# atmega.net
KiCad netlist of a schematic drawn in Altium Designer
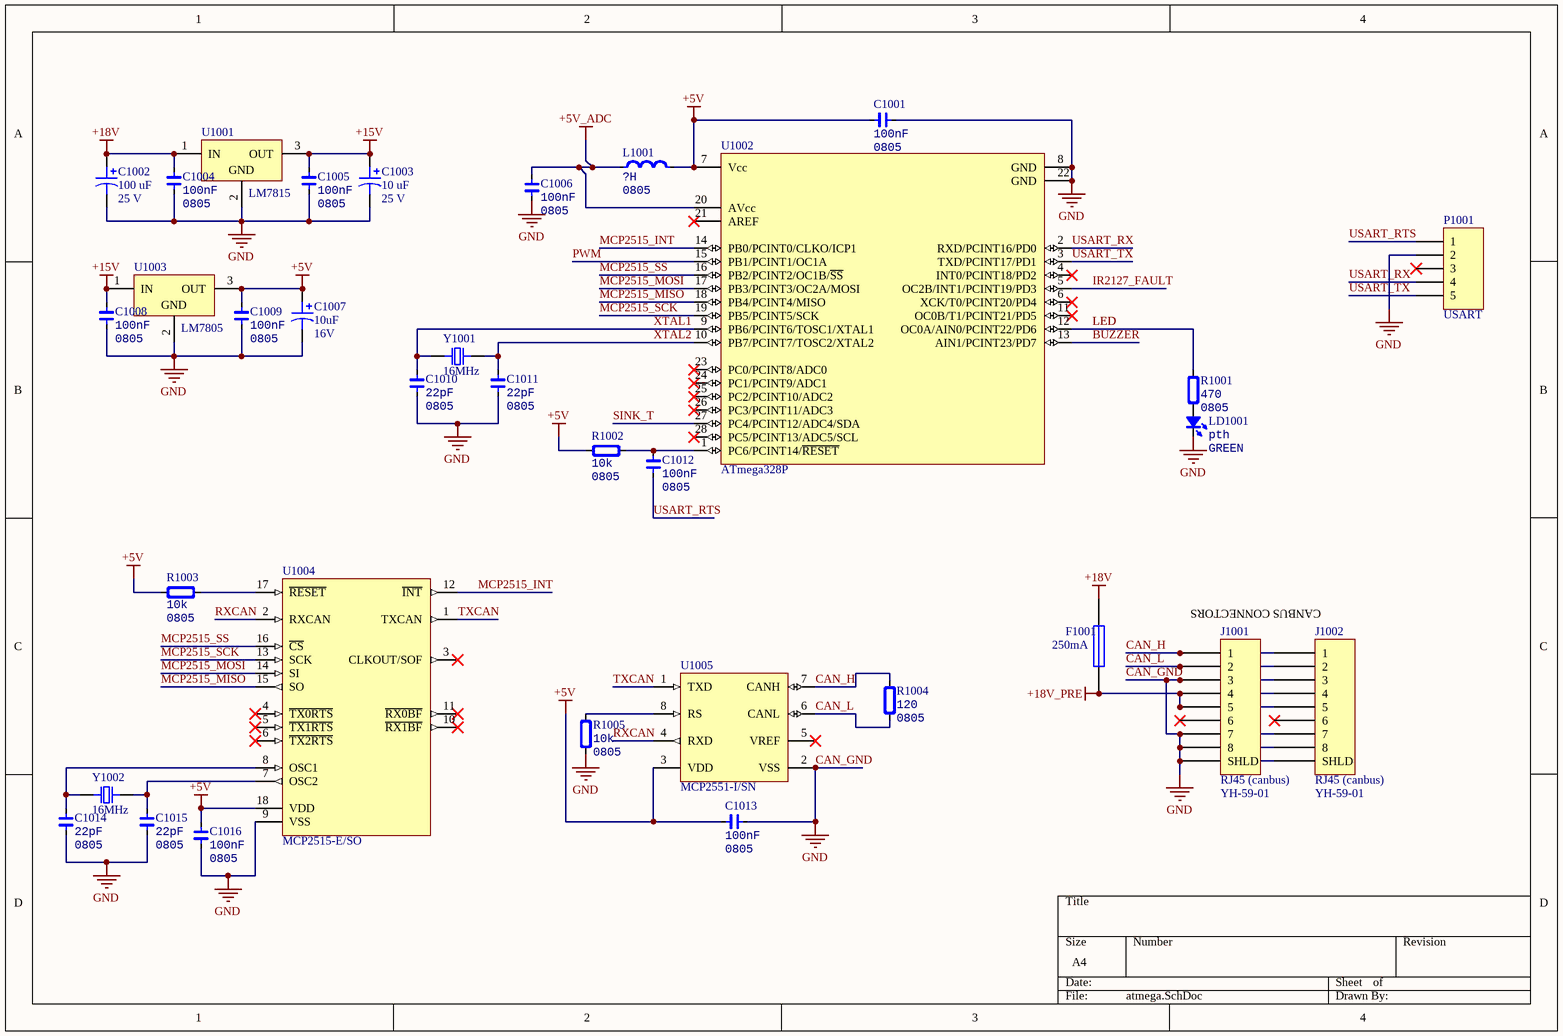
[diagram p0: atmega.SchDoc]

(export (version "E")
  (design (tool "Eeschema 10.0.6"))
  (components
    (comp (ref "C1001")
      (value "100nF")
      (footprint "0805C")
      (description "Capacitor")
      (fields (field (name "TYPE") "0805"))
      (libsource (lib "") (part "Cap_0805_2"))
    )
    (comp (ref "C1002")
      (value "100 uF")
      (footprint "CP3.5mm-8.0mm")
      (description "Solid Aluminum Capacitor with Organic Semiconductor Electrolyte: 100uF, 10V, Bulk Pack")
      (fields (field (name "VOLTAGE") "25 V") (field (name "Comment") "CapacitorPol"))
      (libsource (lib "R2R - Nova") (part "CapacitorPol"))
    )
    (comp (ref "C1003")
      (value "10 uF")
      (footprint "CP3.5mm-8.0mm")
      (description "Solid Aluminum Capacitor with Organic Semiconductor Electrolyte: 100uF, 10V, Bulk Pack")
      (fields (field (name "VOLTAGE") "25 V") (field (name "Comment") "CapacitorPol"))
      (libsource (lib "R2R - Nova") (part "CapacitorPol"))
    )
    (comp (ref "C1004")
      (value "100nF")
      (footprint "0805C")
      (description "Capacitor")
      (fields (field (name "TYPE") "0805"))
      (libsource (lib "SCH_Passive") (part "Cap_0805"))
    )
    (comp (ref "C1005")
      (value "100nF")
      (footprint "0805C")
      (description "Capacitor")
      (fields (field (name "TYPE") "0805"))
      (libsource (lib "SCH_Passive") (part "Cap_0805"))
    )
    (comp (ref "C1006")
      (value "100nF")
      (footprint "0805C")
      (description "Capacitor")
      (fields (field (name "TYPE") "0805"))
      (libsource (lib "SCH_Passive") (part "Cap_0805"))
    )
    (comp (ref "C1007")
      (value "10uF")
      (footprint "CP3.5mm-8.0mm")
      (description "Solid Aluminum Capacitor with Organic Semiconductor Electrolyte: 100uF, 10V, Bulk Pack")
      (fields (field (name "VOLTAGE") "16V") (field (name "Comment") "CapacitorPol"))
      (libsource (lib "R2R - Nova") (part "CapacitorPol"))
    )
    (comp (ref "C1008")
      (value "100nF")
      (footprint "0805C")
      (description "Capacitor")
      (fields (field (name "TYPE") "0805"))
      (libsource (lib "SCH_Passive") (part "Cap_0805"))
    )
    (comp (ref "C1009")
      (value "100nF")
      (footprint "0805C")
      (description "Capacitor")
      (fields (field (name "TYPE") "0805"))
      (libsource (lib "SCH_Passive") (part "Cap_0805"))
    )
    (comp (ref "C1010")
      (value "22pF")
      (footprint "0805C")
      (description "Capacitor")
      (fields (field (name "TYPE") "0805"))
      (libsource (lib "SCH_Passive") (part "Cap_0805"))
    )
    (comp (ref "C1011")
      (value "22pF")
      (footprint "0805C")
      (description "Capacitor")
      (fields (field (name "TYPE") "0805"))
      (libsource (lib "SCH_Passive") (part "Cap_0805"))
    )
    (comp (ref "C1012")
      (value "100nF")
      (footprint "0805C")
      (description "Capacitor")
      (fields (field (name "TYPE") "0805"))
      (libsource (lib "") (part "Cap_0805_1"))
    )
    (comp (ref "C1013")
      (value "100nF")
      (footprint "0805C")
      (description "Capacitor")
      (fields (field (name "TYPE") "0805"))
      (libsource (lib "") (part "Cap_0805_2"))
    )
    (comp (ref "C1014")
      (value "22pF")
      (footprint "0805C")
      (description "Capacitor")
      (fields (field (name "TYPE") "0805"))
      (libsource (lib "SCH_Passive") (part "Cap_0805"))
    )
    (comp (ref "C1015")
      (value "22pF")
      (footprint "0805C")
      (description "Capacitor")
      (fields (field (name "TYPE") "0805"))
      (libsource (lib "SCH_Passive") (part "Cap_0805"))
    )
    (comp (ref "C1016")
      (value "100nF")
      (footprint "0805C")
      (description "Capacitor")
      (fields (field (name "TYPE") "0805"))
      (libsource (lib "") (part "Cap_0805_1"))
    )
    (comp (ref "F1001")
      (value "250mA")
      (footprint "Porta Fusivel")
      (description "Fuse")
      (libsource (lib "Miscellaneous Devices") (part "Fuse 1"))
    )
    (comp (ref "J1001")
      (value "RJ45 (canbus)")
      (footprint "ASSMANN A-2004-2-4-LP/FS")
      (description "YH-59-01")
      (fields (field (name "ALTIUM_VALUE") "YH-59-01"))
      (libsource (lib "Connectors") (part "Modular Jack with Shield"))
    )
    (comp (ref "J1002")
      (value "RJ45 (canbus)")
      (footprint "ASSMANN A-2004-2-4-LP/FS")
      (description "YH-59-01")
      (fields (field (name "ALTIUM_VALUE") "YH-59-01"))
      (libsource (lib "Connectors") (part "Modular Jack with Shield"))
    )
    (comp (ref "L1001")
      (value "?H")
      (footprint "0805L")
      (description "Inductor")
      (fields (field (name "TYPE") "0805"))
      (libsource (lib "SCH_Passive") (part "Ind_0805"))
    )
    (comp (ref "LD1001")
      (value "GREEN")
      (footprint "LED3MM")
      (description "LED")
      (fields (field (name "TYPE") "pth"))
      (libsource (lib "SCH_Active") (part "LED_0805"))
    )
    (comp (ref "P1001")
      (value "USART")
      (footprint "Zenite_Footprints:HDR1X5")
      (description "Header, 5-Pin")
      (libsource (lib "R2R - Nova") (part "Header 5"))
    )
    (comp (ref "R1001")
      (value "470")
      (footprint "0805R")
      (description "Resistor")
      (fields (field (name "TYPE") "0805"))
      (libsource (lib "SCH_Passive") (part "Res_0805"))
    )
    (comp (ref "R1002")
      (value "10k")
      (footprint "0805R")
      (description "Resistor")
      (fields (field (name "TYPE") "0805"))
      (libsource (lib "SCH_Passive") (part "Res_0805"))
    )
    (comp (ref "R1003")
      (value "10k")
      (footprint "0805R")
      (description "Resistor")
      (fields (field (name "TYPE") "0805"))
      (libsource (lib "SCH_Passive") (part "Res_0805"))
    )
    (comp (ref "R1004")
      (value "120")
      (footprint "0805R")
      (description "Resistor")
      (fields (field (name "TYPE") "0805"))
      (libsource (lib "SCH_Passive") (part "Res_0805"))
    )
    (comp (ref "R1005")
      (value "10k")
      (footprint "0805R")
      (description "Resistor")
      (fields (field (name "TYPE") "0805"))
      (libsource (lib "SCH_Passive") (part "Res_0805"))
    )
    (comp (ref "U1001")
      (value "LM7815")
      (footprint "TO220_deitado")
      (description "Positive-Voltage Regulator")
      (libsource (lib "TI Power Mgt Voltage Regulator") (part "µA7805CKC"))
    )
    (comp (ref "U1002")
      (value "ATmega328P")
      (footprint "DIP28-300(100)")
      (libsource (lib "R2R - Nova") (part "ATmega328P"))
    )
    (comp (ref "U1003")
      (value "LM7805")
      (footprint "TO220_deitado")
      (description "Positive-Voltage Regulator")
      (libsource (lib "TI Power Mgt Voltage Regulator") (part "µA7805CKC"))
    )
    (comp (ref "U1004")
      (value "MCP2515-E/SO")
      (footprint "WSO18_L")
      (description "Stand-Alone CAN Controller With SPI Interface, 18-Pin SOIC, Extended Temperature")
      (libsource (lib "Altium Content Vault") (part "COM-CAN-MCP2515-18"))
    )
    (comp (ref "U1005")
      (value "MCP2551-I/SN")
      (footprint "SOIC08-150(50)")
      (libsource (lib "Altium Content Vault") (part "MCHP-MCP2551-SN8"))
    )
    (comp (ref "Y1001")
      (value "16MHz")
      (footprint "HC49-US-THT")
      (description "Crystal")
      (libsource (lib "R2R - Nova") (part "Crystal"))
    )
    (comp (ref "Y1002")
      (value "16MHz")
      (footprint "HC49-US-THT")
      (description "Crystal")
      (libsource (lib "R2R - Nova") (part "Crystal"))
    )
  )
  (nets
    (net (code "1") (name "+5V") (class "Default")
      (node (ref "C1001") (pin "1") (pinfunction "1_1") (pintype "passive"))
      (node (ref "C1007") (pin "1") (pinfunction "1_1") (pintype "passive"))
      (node (ref "C1009") (pin "2") (pinfunction "2_2") (pintype "passive"))
      (node (ref "C1013") (pin "1") (pinfunction "1_1") (pintype "passive"))
      (node (ref "C1016") (pin "1") (pinfunction "1_1") (pintype "passive"))
      (node (ref "L1001") (pin "2") (pinfunction "2_2") (pintype "passive"))
      (node (ref "R1002") (pin "1") (pinfunction "1_1") (pintype "passive"))
      (node (ref "R1003") (pin "1") (pinfunction "1_1") (pintype "passive"))
      (node (ref "U1002") (pin "7") (pinfunction "Vcc_7") (pintype "passive"))
      (node (ref "U1003") (pin "3") (pinfunction "OUT_3") (pintype "power_in"))
      (node (ref "U1004") (pin "18") (pinfunction "VDD_18") (pintype "power_in"))
      (node (ref "U1005") (pin "3") (pinfunction "VDD_3") (pintype "power_in"))
    )
    (net (code "2") (name "+5V_ADC") (class "Default")
      (node (ref "C1006") (pin "2") (pinfunction "2_2") (pintype "passive"))
      (node (ref "L1001") (pin "1") (pinfunction "1_1") (pintype "passive"))
      (node (ref "U1002") (pin "20") (pinfunction "AVcc_20") (pintype "passive"))
    )
    (net (code "3") (name "+15V") (class "Default")
      (node (ref "C1003") (pin "1") (pinfunction "1_1") (pintype "passive"))
      (node (ref "C1005") (pin "2") (pinfunction "2_2") (pintype "passive"))
      (node (ref "C1008") (pin "2") (pinfunction "2_2") (pintype "passive"))
      (node (ref "U1001") (pin "3") (pinfunction "OUT_3") (pintype "power_in"))
      (node (ref "U1003") (pin "1") (pinfunction "IN_1") (pintype "power_in"))
    )
    (net (code "4") (name "+18V") (class "Default")
      (node (ref "C1002") (pin "1") (pinfunction "1_1") (pintype "passive"))
      (node (ref "C1004") (pin "2") (pinfunction "2_2") (pintype "passive"))
      (node (ref "F1001") (pin "1") (pinfunction "1_1") (pintype "passive"))
      (node (ref "U1001") (pin "1") (pinfunction "IN_1") (pintype "power_in"))
    )
    (net (code "5") (name "+18V_PRE") (class "Default")
      (node (ref "F1001") (pin "2") (pinfunction "2_2") (pintype "passive"))
      (node (ref "J1001") (pin "4") (pinfunction "4_4") (pintype "passive"))
      (node (ref "J1001") (pin "5") (pinfunction "5_5") (pintype "passive"))
      (node (ref "J1002") (pin "4") (pinfunction "4_4") (pintype "passive"))
      (node (ref "J1002") (pin "5") (pinfunction "5_5") (pintype "passive"))
    )
    (net (code "6") (name "/BUZZER") (class "Default")
      (node (ref "U1002") (pin "13") (pinfunction "AIN1/PCINT23/PD7_13") (pintype "bidirectional"))
    )
    (net (code "7") (name "/CAN_H") (class "Default")
      (node (ref "J1001") (pin "1") (pinfunction "1_1") (pintype "passive"))
      (node (ref "J1002") (pin "1") (pinfunction "1_1") (pintype "passive"))
      (node (ref "R1004") (pin "2") (pinfunction "2_2") (pintype "passive"))
      (node (ref "U1005") (pin "7") (pinfunction "CANH_7") (pintype "bidirectional"))
    )
    (net (code "8") (name "/CAN_L") (class "Default")
      (node (ref "J1001") (pin "2") (pinfunction "2_2") (pintype "passive"))
      (node (ref "J1002") (pin "2") (pinfunction "2_2") (pintype "passive"))
      (node (ref "R1004") (pin "1") (pinfunction "1_1") (pintype "passive"))
      (node (ref "U1005") (pin "6") (pinfunction "CANL_6") (pintype "bidirectional"))
    )
    (net (code "9") (name "/IR2127_FAULT") (class "Default")
      (node (ref "U1002") (pin "5") (pinfunction "OC2B/INT1/PCINT19/PD3_5") (pintype "bidirectional"))
    )
    (net (code "10") (name "/LED") (class "Default")
      (node (ref "R1001") (pin "2") (pinfunction "2_2") (pintype "passive"))
      (node (ref "U1002") (pin "12") (pinfunction "OC0A/AIN0/PCINT22/PD6_12") (pintype "bidirectional"))
    )
    (net (code "11") (name "/MCP2515_INT") (class "Default")
      (node (ref "U1002") (pin "14") (pinfunction "PB0/PCINT0/CLKO/ICP1_14") (pintype "bidirectional"))
      (node (ref "U1004") (pin "12") (pinfunction "~{INT}_12") (pintype "output"))
    )
    (net (code "12") (name "/MCP2515_MISO") (class "Default")
      (node (ref "U1002") (pin "18") (pinfunction "PB4/PCINT4/MISO_18") (pintype "bidirectional"))
      (node (ref "U1004") (pin "15") (pinfunction "SO_15") (pintype "output"))
    )
    (net (code "13") (name "/MCP2515_MOSI") (class "Default")
      (node (ref "U1002") (pin "17") (pinfunction "PB3/PCINT3/OC2A/MOSI_17") (pintype "bidirectional"))
      (node (ref "U1004") (pin "14") (pinfunction "SI_14") (pintype "input"))
    )
    (net (code "14") (name "/MCP2515_SCK") (class "Default")
      (node (ref "U1002") (pin "19") (pinfunction "PB5/PCINT5/SCK_19") (pintype "bidirectional"))
      (node (ref "U1004") (pin "13") (pinfunction "SCK_13") (pintype "input"))
    )
    (net (code "15") (name "/MCP2515_SS") (class "Default")
      (node (ref "U1002") (pin "16") (pinfunction "PB2/PCINT2/OC1B/~{SS}_16") (pintype "bidirectional"))
      (node (ref "U1004") (pin "16") (pinfunction "~{CS}_16") (pintype "input"))
    )
    (net (code "16") (name "/PWM") (class "Default")
      (node (ref "U1002") (pin "15") (pinfunction "PB1/PCINT1/OC1A_15") (pintype "bidirectional"))
    )
    (net (code "17") (name "/RXCAN") (class "Default")
      (node (ref "U1004") (pin "2") (pinfunction "RXCAN_2") (pintype "input"))
      (node (ref "U1005") (pin "4") (pinfunction "RXD_4") (pintype "output"))
    )
    (net (code "18") (name "/SINK_T") (class "Default")
      (node (ref "U1002") (pin "27") (pinfunction "PC4/PCINT12/ADC4/SDA_27") (pintype "bidirectional"))
    )
    (net (code "19") (name "/TXCAN") (class "Default")
      (node (ref "U1004") (pin "1") (pinfunction "TXCAN_1") (pintype "output"))
      (node (ref "U1005") (pin "1") (pinfunction "TXD_1") (pintype "input"))
    )
    (net (code "20") (name "/USART_RTS") (class "Default")
      (node (ref "C1012") (pin "2") (pinfunction "2_2") (pintype "passive"))
      (node (ref "P1001") (pin "1") (pinfunction "1_1") (pintype "passive"))
    )
    (net (code "21") (name "/USART_RX") (class "Default")
      (node (ref "P1001") (pin "4") (pinfunction "4_4") (pintype "passive"))
      (node (ref "U1002") (pin "2") (pinfunction "RXD/PCINT16/PD0_2") (pintype "bidirectional"))
    )
    (net (code "22") (name "/USART_TX") (class "Default")
      (node (ref "P1001") (pin "5") (pinfunction "5_5") (pintype "passive"))
      (node (ref "U1002") (pin "3") (pinfunction "TXD/PCINT17/PD1_3") (pintype "bidirectional"))
    )
    (net (code "23") (name "/XTAL1") (class "Default")
      (node (ref "C1010") (pin "2") (pinfunction "2_2") (pintype "passive"))
      (node (ref "U1002") (pin "9") (pinfunction "PB6/PCINT6/TOSC1/XTAL1_9") (pintype "bidirectional"))
      (node (ref "Y1001") (pin "1") (pinfunction "1_1") (pintype "passive"))
    )
    (net (code "24") (name "/XTAL2") (class "Default")
      (node (ref "C1011") (pin "2") (pinfunction "2_2") (pintype "passive"))
      (node (ref "U1002") (pin "10") (pinfunction "PB7/PCINT7/TOSC2/XTAL2_10") (pintype "bidirectional"))
      (node (ref "Y1001") (pin "2") (pinfunction "2_2") (pintype "passive"))
    )
    (net (code "25") (name "GND") (class "Default")
      (node (ref "C1001") (pin "2") (pinfunction "2_2") (pintype "passive"))
      (node (ref "C1002") (pin "2") (pinfunction "2_2") (pintype "passive"))
      (node (ref "C1003") (pin "2") (pinfunction "2_2") (pintype "passive"))
      (node (ref "C1004") (pin "1") (pinfunction "1_1") (pintype "passive"))
      (node (ref "C1005") (pin "1") (pinfunction "1_1") (pintype "passive"))
      (node (ref "C1006") (pin "1") (pinfunction "1_1") (pintype "passive"))
      (node (ref "C1007") (pin "2") (pinfunction "2_2") (pintype "passive"))
      (node (ref "C1008") (pin "1") (pinfunction "1_1") (pintype "passive"))
      (node (ref "C1009") (pin "1") (pinfunction "1_1") (pintype "passive"))
      (node (ref "C1010") (pin "1") (pinfunction "1_1") (pintype "passive"))
      (node (ref "C1011") (pin "1") (pinfunction "1_1") (pintype "passive"))
      (node (ref "C1013") (pin "2") (pinfunction "2_2") (pintype "passive"))
      (node (ref "C1014") (pin "1") (pinfunction "1_1") (pintype "passive"))
      (node (ref "C1015") (pin "1") (pinfunction "1_1") (pintype "passive"))
      (node (ref "C1016") (pin "2") (pinfunction "2_2") (pintype "passive"))
      (node (ref "J1001") (pin "3") (pinfunction "3_3") (pintype "passive"))
      (node (ref "J1001") (pin "7") (pinfunction "7_7") (pintype "passive"))
      (node (ref "J1001") (pin "8") (pinfunction "8_8") (pintype "passive"))
      (node (ref "J1001") (pin "S") (pinfunction "SHLD_S") (pintype "passive"))
      (node (ref "J1002") (pin "3") (pinfunction "3_3") (pintype "passive"))
      (node (ref "J1002") (pin "7") (pinfunction "7_7") (pintype "passive"))
      (node (ref "J1002") (pin "8") (pinfunction "8_8") (pintype "passive"))
      (node (ref "J1002") (pin "S") (pinfunction "SHLD_S") (pintype "passive"))
      (node (ref "LD1001") (pin "2") (pinfunction "K_2") (pintype "passive"))
      (node (ref "P1001") (pin "2") (pinfunction "2_2") (pintype "passive"))
      (node (ref "R1005") (pin "2") (pinfunction "2_2") (pintype "passive"))
      (node (ref "U1001") (pin "2") (pinfunction "GND_2") (pintype "power_in"))
      (node (ref "U1002") (pin "22") (pinfunction "GND_22") (pintype "passive"))
      (node (ref "U1002") (pin "8") (pinfunction "GND_8") (pintype "passive"))
      (node (ref "U1003") (pin "2") (pinfunction "GND_2") (pintype "power_in"))
      (node (ref "U1004") (pin "9") (pinfunction "VSS_9") (pintype "power_in"))
      (node (ref "U1005") (pin "2") (pinfunction "VSS_2") (pintype "power_in"))
    )
    (net (code "26") (name "Net-(LD1001-A)") (class "Default")
      (node (ref "LD1001") (pin "1") (pinfunction "A_1") (pintype "passive"))
      (node (ref "R1001") (pin "1") (pinfunction "1_1") (pintype "passive"))
    )
    (net (code "27") (name "Net-(U1002-PC6{slash}PCINT14{slash}~{RESET})") (class "Default")
      (node (ref "C1012") (pin "1") (pinfunction "1_1") (pintype "passive"))
      (node (ref "R1002") (pin "2") (pinfunction "2_2") (pintype "passive"))
      (node (ref "U1002") (pin "1") (pinfunction "PC6/PCINT14/~{RESET}_1") (pintype "bidirectional"))
    )
    (net (code "28") (name "Net-(U1004-OSC1)") (class "Default")
      (node (ref "C1014") (pin "2") (pinfunction "2_2") (pintype "passive"))
      (node (ref "U1004") (pin "8") (pinfunction "OSC1_8") (pintype "input"))
      (node (ref "Y1002") (pin "1") (pinfunction "1_1") (pintype "passive"))
    )
    (net (code "29") (name "Net-(U1004-OSC2)") (class "Default")
      (node (ref "C1015") (pin "2") (pinfunction "2_2") (pintype "passive"))
      (node (ref "U1004") (pin "7") (pinfunction "OSC2_7") (pintype "output"))
      (node (ref "Y1002") (pin "2") (pinfunction "2_2") (pintype "passive"))
    )
    (net (code "30") (name "Net-(U1004-~{RESET})") (class "Default")
      (node (ref "R1003") (pin "2") (pinfunction "2_2") (pintype "passive"))
      (node (ref "U1004") (pin "17") (pinfunction "~{RESET}_17") (pintype "input"))
    )
    (net (code "31") (name "Net-(U1005-RS)") (class "Default")
      (node (ref "R1005") (pin "1") (pinfunction "1_1") (pintype "passive"))
      (node (ref "U1005") (pin "8") (pinfunction "RS_8") (pintype "input"))
    )
    (net (code "32") (name "unconnected-(J1001-Pad6)") (class "Default")
      (node (ref "J1001") (pin "6") (pinfunction "6_6") (pintype "passive+no_connect"))
    )
    (net (code "33") (name "unconnected-(J1002-Pad6)") (class "Default")
      (node (ref "J1002") (pin "6") (pinfunction "6_6") (pintype "passive+no_connect"))
    )
    (net (code "34") (name "unconnected-(P1001-Pad3)") (class "Default")
      (node (ref "P1001") (pin "3") (pinfunction "3_3") (pintype "passive+no_connect"))
    )
    (net (code "35") (name "unconnected-(U1002-AREF-Pad21)") (class "Default")
      (node (ref "U1002") (pin "21") (pinfunction "AREF_21") (pintype "passive+no_connect"))
    )
    (net (code "36") (name "unconnected-(U1002-INT0{slash}PCINT18{slash}PD2-Pad4)") (class "Default")
      (node (ref "U1002") (pin "4") (pinfunction "INT0/PCINT18/PD2_4") (pintype "bidirectional+no_connect"))
    )
    (net (code "37") (name "unconnected-(U1002-OC0B{slash}T1{slash}PCINT21{slash}PD5-Pad11)") (class "Default")
      (node (ref "U1002") (pin "11") (pinfunction "OC0B/T1/PCINT21/PD5_11") (pintype "bidirectional+no_connect"))
    )
    (net (code "38") (name "unconnected-(U1002-PC0{slash}PCINT8{slash}ADC0-Pad23)") (class "Default")
      (node (ref "U1002") (pin "23") (pinfunction "PC0/PCINT8/ADC0_23") (pintype "bidirectional+no_connect"))
    )
    (net (code "39") (name "unconnected-(U1002-PC1{slash}PCINT9{slash}ADC1-Pad24)") (class "Default")
      (node (ref "U1002") (pin "24") (pinfunction "PC1/PCINT9/ADC1_24") (pintype "bidirectional+no_connect"))
    )
    (net (code "40") (name "unconnected-(U1002-PC2{slash}PCINT10{slash}ADC2-Pad25)") (class "Default")
      (node (ref "U1002") (pin "25") (pinfunction "PC2/PCINT10/ADC2_25") (pintype "bidirectional+no_connect"))
    )
    (net (code "41") (name "unconnected-(U1002-PC3{slash}PCINT11{slash}ADC3-Pad26)") (class "Default")
      (node (ref "U1002") (pin "26") (pinfunction "PC3/PCINT11/ADC3_26") (pintype "bidirectional+no_connect"))
    )
    (net (code "42") (name "unconnected-(U1002-PC5{slash}PCINT13{slash}ADC5{slash}SCL-Pad28)") (class "Default")
      (node (ref "U1002") (pin "28") (pinfunction "PC5/PCINT13/ADC5/SCL_28") (pintype "bidirectional+no_connect"))
    )
    (net (code "43") (name "unconnected-(U1002-XCK{slash}T0{slash}PCINT20{slash}PD4-Pad6)") (class "Default")
      (node (ref "U1002") (pin "6") (pinfunction "XCK/T0/PCINT20/PD4_6") (pintype "bidirectional+no_connect"))
    )
    (net (code "44") (name "unconnected-(U1004-CLKOUT{slash}SOF-Pad3)") (class "Default")
      (node (ref "U1004") (pin "3") (pinfunction "CLKOUT/SOF_3") (pintype "output+no_connect"))
    )
    (net (code "45") (name "unconnected-(U1004-~{RX0BF}-Pad11)") (class "Default")
      (node (ref "U1004") (pin "11") (pinfunction "~{RX0BF}_11") (pintype "output+no_connect"))
    )
    (net (code "46") (name "unconnected-(U1004-~{RX1BF}-Pad10)") (class "Default")
      (node (ref "U1004") (pin "10") (pinfunction "~{RX1BF}_10") (pintype "output+no_connect"))
    )
    (net (code "47") (name "unconnected-(U1004-~{TX0RTS}-Pad4)") (class "Default")
      (node (ref "U1004") (pin "4") (pinfunction "~{TX0RTS}_4") (pintype "input+no_connect"))
    )
    (net (code "48") (name "unconnected-(U1004-~{TX1RTS}-Pad5)") (class "Default")
      (node (ref "U1004") (pin "5") (pinfunction "~{TX1RTS}_5") (pintype "input+no_connect"))
    )
    (net (code "49") (name "unconnected-(U1004-~{TX2RTS}-Pad6)") (class "Default")
      (node (ref "U1004") (pin "6") (pinfunction "~{TX2RTS}_6") (pintype "input+no_connect"))
    )
    (net (code "50") (name "unconnected-(U1005-VREF-Pad5)") (class "Default")
      (node (ref "U1005") (pin "5") (pinfunction "VREF_5") (pintype "power_in+no_connect"))
    )
  )
)
